# Schematic_STM32.net
KiCad netlist of a schematic drawn in Altium Designer
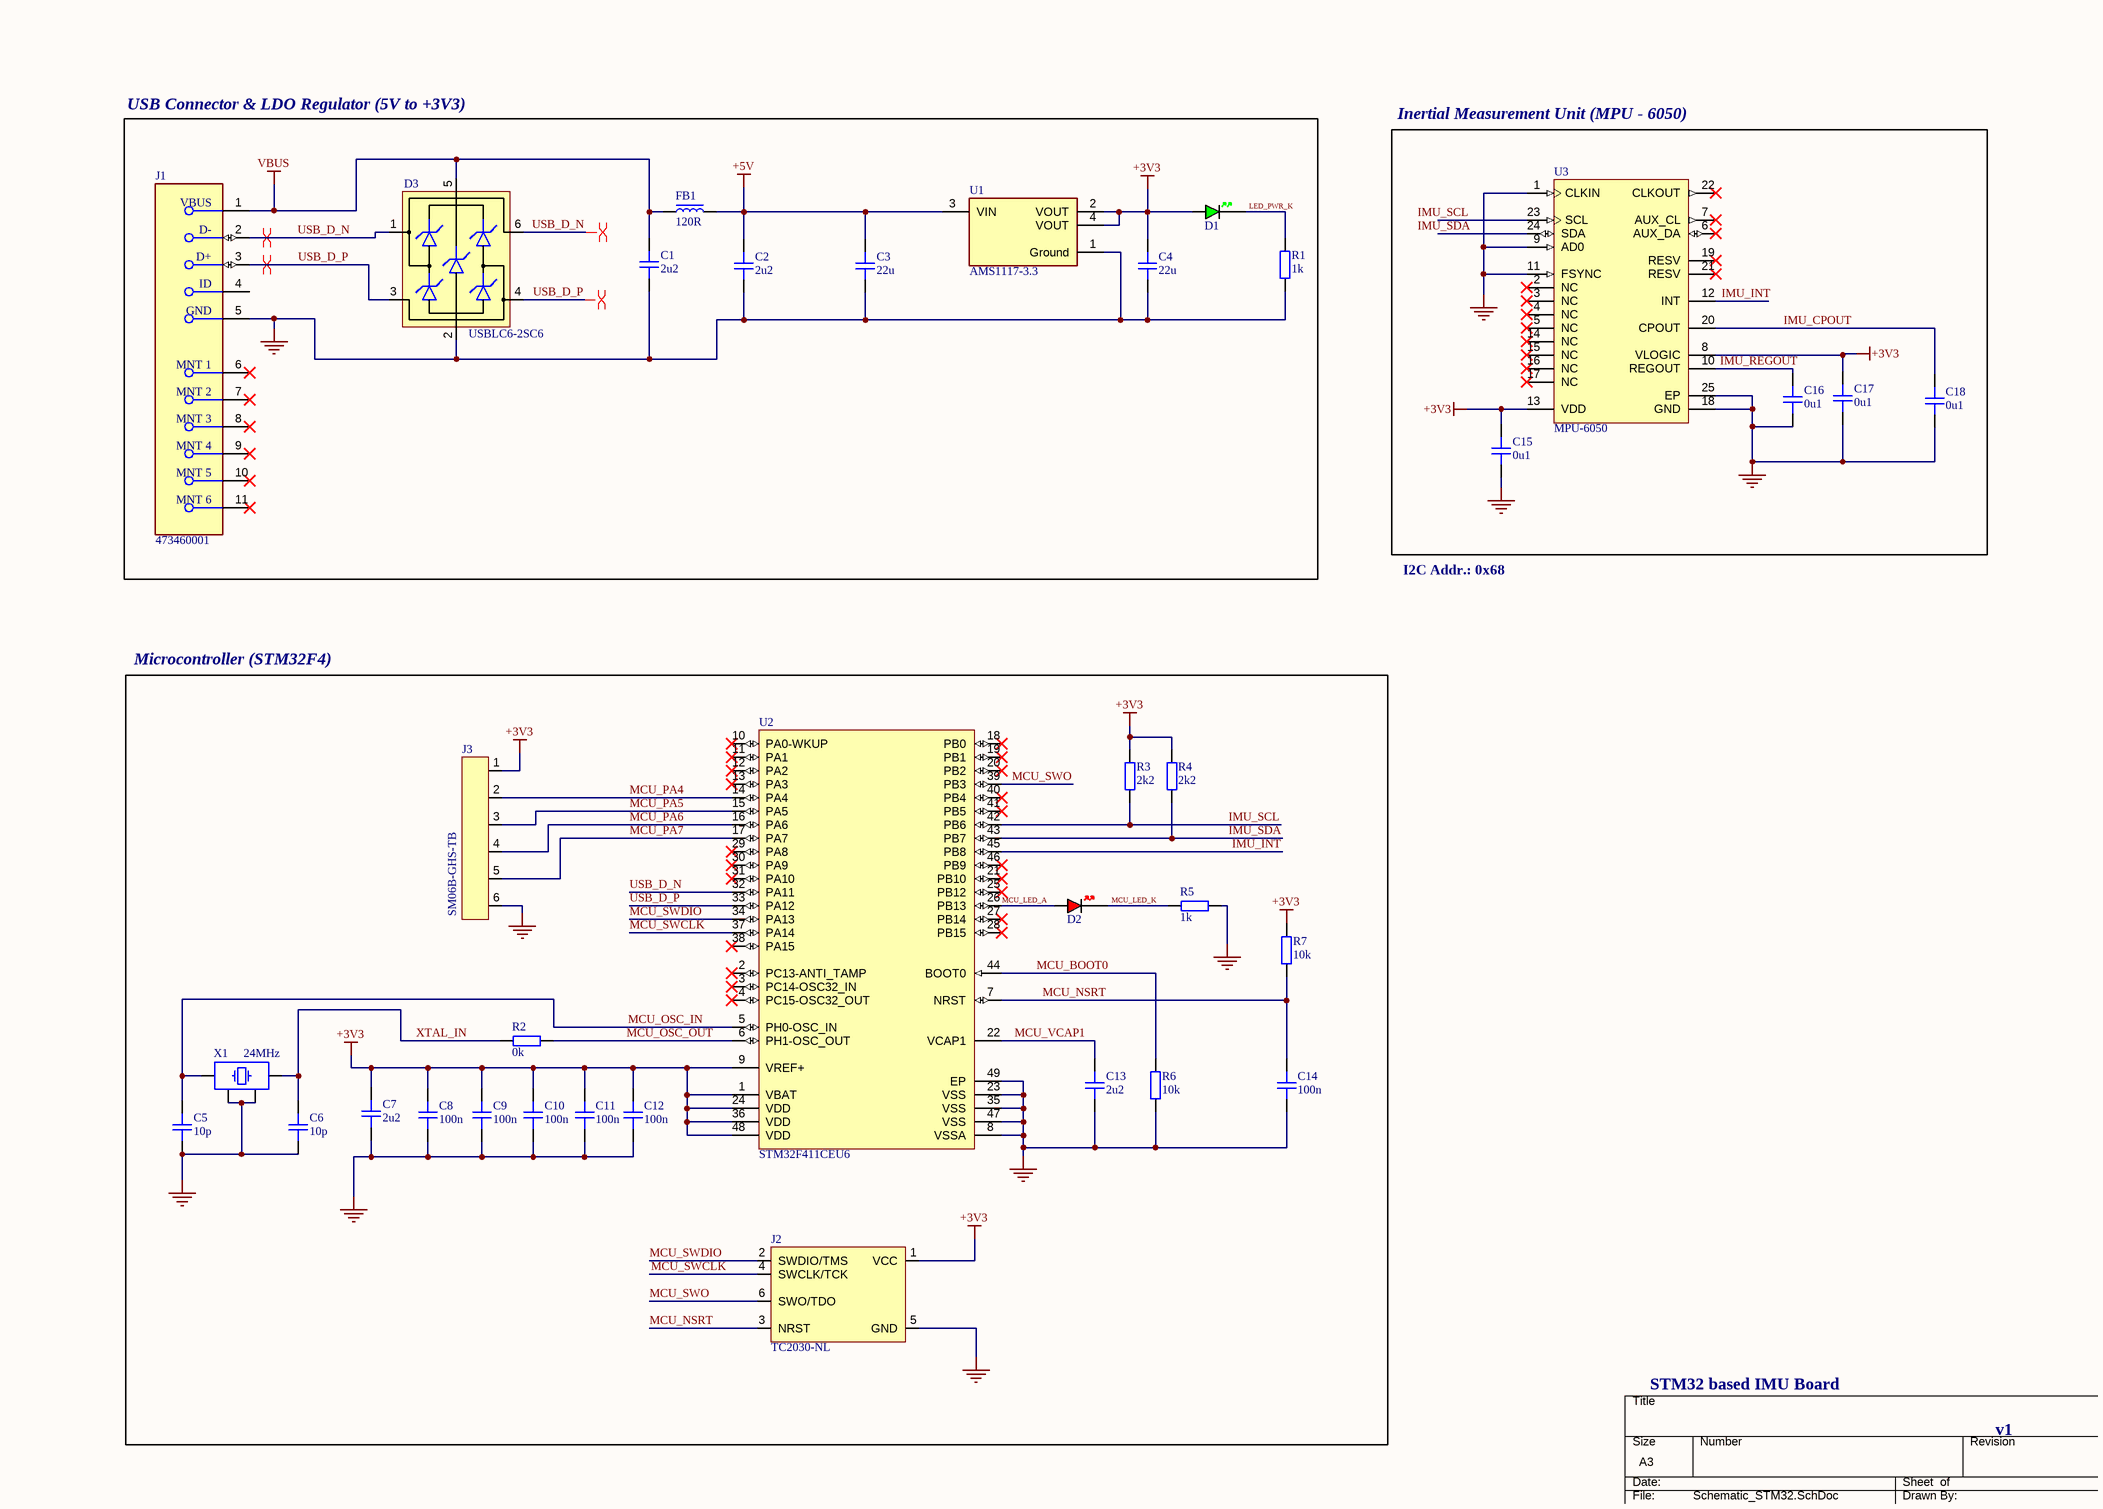
[diagram p0: Schematic_STM32.SchDoc]

(export (version "E")
  (design (tool "Eeschema 10.0.6"))
  (components
    (comp (ref "C1")
      (value "2u2")
      (footprint "CAP_0603")
      (description "Capacitor SMD 0603")
      (libsource (lib "Schematic-Lib-PhilsLab") (part "CAP_0603"))
    )
    (comp (ref "C2")
      (value "2u2")
      (footprint "CAP_0603")
      (description "Capacitor SMD 0603")
      (libsource (lib "Schematic-Lib-PhilsLab") (part "CAP_0603"))
    )
    (comp (ref "C3")
      (value "22u")
      (footprint "CAP_0805")
      (description "Capacitor SMD 0805")
      (libsource (lib "Schematic-Lib-PhilsLab") (part "CAP_0805"))
    )
    (comp (ref "C4")
      (value "22u")
      (footprint "CAP_0805")
      (description "Capacitor SMD 0805")
      (libsource (lib "Schematic-Lib-PhilsLab") (part "CAP_0805"))
    )
    (comp (ref "C5")
      (value "10p")
      (footprint "CAP_0402")
      (description "Capacitor SMD 0402")
      (libsource (lib "Schematic-Lib-PhilsLab") (part "CAP_0402"))
    )
    (comp (ref "C6")
      (value "10p")
      (footprint "CAP_0402")
      (description "Capacitor SMD 0402")
      (libsource (lib "Schematic-Lib-PhilsLab") (part "CAP_0402"))
    )
    (comp (ref "C7")
      (value "2u2")
      (footprint "CAP_0603")
      (description "Capacitor SMD 0603")
      (libsource (lib "Schematic-Lib-PhilsLab") (part "CAP_0603"))
    )
    (comp (ref "C8")
      (value "100n")
      (footprint "CAP_0402")
      (description "Capacitor SMD 0402")
      (libsource (lib "Schematic-Lib-PhilsLab") (part "CAP_0402"))
    )
    (comp (ref "C9")
      (value "100n")
      (footprint "CAP_0402")
      (description "Capacitor SMD 0402")
      (libsource (lib "Schematic-Lib-PhilsLab") (part "CAP_0402"))
    )
    (comp (ref "C10")
      (value "100n")
      (footprint "CAP_0402")
      (description "Capacitor SMD 0402")
      (libsource (lib "Schematic-Lib-PhilsLab") (part "CAP_0402"))
    )
    (comp (ref "C11")
      (value "100n")
      (footprint "CAP_0402")
      (description "Capacitor SMD 0402")
      (libsource (lib "Schematic-Lib-PhilsLab") (part "CAP_0402"))
    )
    (comp (ref "C12")
      (value "100n")
      (footprint "CAP_0402")
      (description "Capacitor SMD 0402")
      (libsource (lib "Schematic-Lib-PhilsLab") (part "CAP_0402"))
    )
    (comp (ref "C13")
      (value "2u2")
      (footprint "CAP_0603")
      (description "Capacitor SMD 0603")
      (libsource (lib "Schematic-Lib-PhilsLab") (part "CAP_0603"))
    )
    (comp (ref "C14")
      (value "100n")
      (footprint "CAP_0402")
      (description "Capacitor SMD 0402")
      (libsource (lib "Schematic-Lib-PhilsLab") (part "CAP_0402"))
    )
    (comp (ref "C15")
      (value "0u1")
      (footprint "CAP_0402")
      (description "Capacitor SMD 0402")
      (libsource (lib "Schematic-Lib-PhilsLab") (part "CAP_0402"))
    )
    (comp (ref "C16")
      (value "0u1")
      (footprint "CAP_0402")
      (description "Capacitor SMD 0402")
      (libsource (lib "Schematic-Lib-PhilsLab") (part "CAP_0402"))
    )
    (comp (ref "C17")
      (value "0u1")
      (footprint "CAP_0402")
      (description "Capacitor SMD 0402")
      (libsource (lib "Schematic-Lib-PhilsLab") (part "CAP_0402"))
    )
    (comp (ref "C18")
      (value "0u1")
      (footprint "CAP_0402")
      (description "Capacitor SMD 0402")
      (libsource (lib "Schematic-Lib-PhilsLab") (part "CAP_0402"))
    )
    (comp (ref "D1")
      (value "GREEN")
      (footprint "LED_0402_GREEN")
      (description "LED 0402 GREEN SMD")
      (libsource (lib "Schematic-Lib-PhilsLab") (part "LED_0402_GREEN"))
    )
    (comp (ref "D2")
      (value "RED")
      (footprint "LED_0402_RED")
      (description "LED 0402 RED SMD")
      (libsource (lib "Schematic-Lib-PhilsLab") (part "LED_0402_RED"))
    )
    (comp (ref "D3")
      (value "USBLC6-2SC6")
      (footprint "SOT-23-6")
      (description "Low-Capacitance ESD Protection USB")
      (fields (field (name "MANUFACTURER") "STMicroelectronics"))
      (libsource (lib "Schematic-Lib-PhilsLab") (part "USBLC6-2SC6"))
    )
    (comp (ref "FB1")
      (value "120R")
      (footprint "FB_0402")
      (description "Ferrite Bead SMD 0402")
      (libsource (lib "Schematic-Lib-PhilsLab") (part "FB_0402"))
    )
    (comp (ref "J1")
      (value "473460001")
      (footprint "FP-473460001-MFG")
      (description "CONN RCPT USB2.0 MICRO B SMD R/A")
      (fields
        (field (name "OCTOPART") "https://octopart.com/47346-0001-molex-7164928")
        (field (name "MANUFACTURER") "Molex")
      )
      (libsource (lib "Altium Content Vault") (part "53ae1f1d9b557310b43ca686e5bb76a"))
    )
    (comp (ref "J2")
      (value "TC2030-NL")
      (footprint "TC2030-NL-FP")
      (description "Tag-Connect No-Solder SWD Debug Connector (No Legs) DO NOT PLACE")
      (fields
        (field (name "MANUFACTURER") "Tag-Connect")
        (field (name "MANUFACTURER PART NUMBER") "TC2030-NL-FP")
      )
      (libsource (lib "Schematic-Lib-PhilsLab") (part "TC2030-NL"))
    )
    (comp (ref "J3")
      (value "SM06B-GHS-TB")
      (footprint "SM06B-GHS-TB")
      (description "Header Connector 6 Position 1.25MM Pitch SMD Horizontal JST GH")
      (fields (field (name "MANUFACTURER") "JST"))
      (libsource (lib "Schematic-Lib-PhilsLab") (part "SM06B-GHS-TB"))
    )
    (comp (ref "R1")
      (value "1k")
      (footprint "RES_0402")
      (description "Resistor SMD 0402")
      (libsource (lib "Schematic-Lib-PhilsLab") (part "RES_0402"))
    )
    (comp (ref "R2")
      (value "0k")
      (footprint "RES_0402")
      (description "Resistor SMD 0402")
      (libsource (lib "Schematic-Lib-PhilsLab") (part "RES_0402"))
    )
    (comp (ref "R3")
      (value "2k2")
      (footprint "RES_0402")
      (description "Resistor SMD 0402")
      (libsource (lib "Schematic-Lib-PhilsLab") (part "RES_0402"))
    )
    (comp (ref "R4")
      (value "2k2")
      (footprint "RES_0402")
      (description "Resistor SMD 0402")
      (libsource (lib "Schematic-Lib-PhilsLab") (part "RES_0402"))
    )
    (comp (ref "R5")
      (value "1k")
      (footprint "RES_0402")
      (description "Resistor SMD 0402")
      (libsource (lib "Schematic-Lib-PhilsLab") (part "RES_0402"))
    )
    (comp (ref "R6")
      (value "10k")
      (footprint "RES_0402")
      (description "Resistor SMD 0402")
      (libsource (lib "Schematic-Lib-PhilsLab") (part "RES_0402"))
    )
    (comp (ref "R7")
      (value "10k")
      (footprint "RES_0402")
      (description "Resistor SMD 0402")
      (libsource (lib "Schematic-Lib-PhilsLab") (part "RES_0402"))
    )
    (comp (ref "U1")
      (value "AMS1117-3.3")
      (footprint "FP-AMS1117-IPC_C")
      (description "LDO Voltage Regulators 1A, 3.3V")
      (fields
        (field (name "OCTOPART") "https://octopart.com/ams1117-3.3-advanced+monolithic+systems-25899300")
        (field (name "MANUFACTURER") "Advanced Monolithic Systems")
      )
      (libsource (lib "Altium Content Vault") (part "8bdbb5f8e77002000e30dd2845d0354"))
    )
    (comp (ref "U2")
      (value "STM32F411CEU6")
      (footprint "STM-UFQFPN48_L")
      (libsource (lib "Altium Content Vault") (part "MC-ARM-STM32F411-UFQFPN48"))
    )
    (comp (ref "U3")
      (value "MPU-6050")
      (footprint "IS-QFN-24_V")
      (fields (field (name "MANUFACTURER") "InvenSense"))
      (libsource (lib "Altium Content Vault") (part "IS-MPU-6050-QFN-24"))
    )
    (comp (ref "X1")
      (value "24MHz")
      (footprint "XTAL_3225")
      (description "Crystal SMD 24MHz 10PPM 7pF 3225")
      (fields
        (field (name "MANUFACTURER") "Epson")
        (field (name "MANUFACTURER PART NUMBER") "TSX-3225 24.0000MF15X-AC")
      )
      (libsource (lib "Schematic-Lib-PhilsLab") (part "TSX-3225_24.0000MF15X-AC"))
    )
  )
  (nets
    (net (code "1") (name "+3V3") (class "Default")
      (node (ref "C10") (pin "2") (pinfunction "2_2") (pintype "passive"))
      (node (ref "C11") (pin "2") (pinfunction "2_2") (pintype "passive"))
      (node (ref "C12") (pin "2") (pinfunction "2_2") (pintype "passive"))
      (node (ref "C15") (pin "2") (pinfunction "2_2") (pintype "passive"))
      (node (ref "C17") (pin "2") (pinfunction "2_2") (pintype "passive"))
      (node (ref "C4") (pin "2") (pinfunction "2_2") (pintype "passive"))
      (node (ref "C7") (pin "2") (pinfunction "2_2") (pintype "passive"))
      (node (ref "C8") (pin "2") (pinfunction "2_2") (pintype "passive"))
      (node (ref "C9") (pin "2") (pinfunction "2_2") (pintype "passive"))
      (node (ref "D1") (pin "A") (pinfunction "A_A") (pintype "passive"))
      (node (ref "J2") (pin "1") (pinfunction "VCC_1") (pintype "passive"))
      (node (ref "J3") (pin "1") (pinfunction "1_1") (pintype "passive"))
      (node (ref "R3") (pin "2") (pinfunction "2_2") (pintype "passive"))
      (node (ref "R4") (pin "2") (pinfunction "2_2") (pintype "passive"))
      (node (ref "R7") (pin "2") (pinfunction "2_2") (pintype "passive"))
      (node (ref "U1") (pin "2") (pinfunction "VOUT_2") (pintype "passive"))
      (node (ref "U1") (pin "4") (pinfunction "VOUT_4") (pintype "passive"))
      (node (ref "U2") (pin "1") (pinfunction "VBAT_1") (pintype "power_in"))
      (node (ref "U2") (pin "24") (pinfunction "VDD_24") (pintype "power_in"))
      (node (ref "U2") (pin "36") (pinfunction "VDD_36") (pintype "power_in"))
      (node (ref "U2") (pin "48") (pinfunction "VDD_48") (pintype "power_in"))
      (node (ref "U2") (pin "9") (pinfunction "VREF+_9") (pintype "power_in"))
      (node (ref "U3") (pin "13") (pinfunction "VDD_13") (pintype "power_in"))
      (node (ref "U3") (pin "8") (pinfunction "VLOGIC_8") (pintype "power_in"))
    )
    (net (code "2") (name "+5V") (class "Default")
      (node (ref "C2") (pin "2") (pinfunction "2_2") (pintype "passive"))
      (node (ref "C3") (pin "2") (pinfunction "2_2") (pintype "passive"))
      (node (ref "FB1") (pin "2") (pinfunction "2_2") (pintype "passive"))
      (node (ref "U1") (pin "3") (pinfunction "VIN_3") (pintype "power_in"))
    )
    (net (code "3") (name "/IMU_CPOUT") (class "Default")
      (node (ref "C18") (pin "2") (pinfunction "2_2") (pintype "passive"))
      (node (ref "U3") (pin "20") (pinfunction "CPOUT_20") (pintype "passive"))
    )
    (net (code "4") (name "/IMU_INT") (class "Default")
      (node (ref "U2") (pin "45") (pinfunction "PB8_45") (pintype "bidirectional"))
      (node (ref "U3") (pin "12") (pinfunction "INT_12") (pintype "open_collector"))
    )
    (net (code "5") (name "/IMU_REGOUT") (class "Default")
      (node (ref "C16") (pin "2") (pinfunction "2_2") (pintype "passive"))
      (node (ref "U3") (pin "10") (pinfunction "REGOUT_10") (pintype "passive"))
    )
    (net (code "6") (name "/IMU_SCL") (class "Default")
      (node (ref "R3") (pin "1") (pinfunction "1_1") (pintype "passive"))
      (node (ref "U2") (pin "42") (pinfunction "PB6_42") (pintype "bidirectional"))
      (node (ref "U3") (pin "23") (pinfunction "SCL_23") (pintype "input"))
    )
    (net (code "7") (name "/IMU_SDA") (class "Default")
      (node (ref "R4") (pin "1") (pinfunction "1_1") (pintype "passive"))
      (node (ref "U2") (pin "43") (pinfunction "PB7_43") (pintype "bidirectional"))
      (node (ref "U3") (pin "24") (pinfunction "SDA_24") (pintype "bidirectional"))
    )
    (net (code "8") (name "/LED_PWR_K") (class "Default")
      (node (ref "D1") (pin "K") (pinfunction "K_K") (pintype "passive"))
      (node (ref "R1") (pin "2") (pinfunction "2_2") (pintype "passive"))
    )
    (net (code "9") (name "/MCU_BOOT0") (class "Default")
      (node (ref "R6") (pin "2") (pinfunction "2_2") (pintype "passive"))
      (node (ref "U2") (pin "44") (pinfunction "BOOT0_44") (pintype "input"))
    )
    (net (code "10") (name "/MCU_LED_A") (class "Default")
      (node (ref "D2") (pin "A") (pinfunction "A_A") (pintype "passive"))
      (node (ref "U2") (pin "26") (pinfunction "PB13_26") (pintype "bidirectional"))
    )
    (net (code "11") (name "/MCU_LED_K") (class "Default")
      (node (ref "D2") (pin "K") (pinfunction "K_K") (pintype "passive"))
      (node (ref "R5") (pin "2") (pinfunction "2_2") (pintype "passive"))
    )
    (net (code "12") (name "/MCU_NSRT") (class "Default")
      (node (ref "C14") (pin "2") (pinfunction "2_2") (pintype "passive"))
      (node (ref "J2") (pin "3") (pinfunction "NRST_3") (pintype "passive"))
      (node (ref "R7") (pin "1") (pinfunction "1_1") (pintype "passive"))
      (node (ref "U2") (pin "7") (pinfunction "NRST_7") (pintype "bidirectional"))
    )
    (net (code "13") (name "/MCU_OSC_IN") (class "Default")
      (node (ref "C5") (pin "2") (pinfunction "2_2") (pintype "passive"))
      (node (ref "U2") (pin "5") (pinfunction "PH0-OSC_IN_5") (pintype "bidirectional"))
      (node (ref "X1") (pin "1") (pinfunction "1_1") (pintype "passive"))
    )
    (net (code "14") (name "/MCU_OSC_OUT") (class "Default")
      (node (ref "R2") (pin "1") (pinfunction "1_1") (pintype "passive"))
      (node (ref "U2") (pin "6") (pinfunction "PH1-OSC_OUT_6") (pintype "bidirectional"))
    )
    (net (code "15") (name "/MCU_PA4") (class "Default")
      (node (ref "J3") (pin "2") (pinfunction "2_2") (pintype "passive"))
      (node (ref "U2") (pin "14") (pinfunction "PA4_14") (pintype "bidirectional"))
    )
    (net (code "16") (name "/MCU_PA5") (class "Default")
      (node (ref "J3") (pin "3") (pinfunction "3_3") (pintype "passive"))
      (node (ref "U2") (pin "15") (pinfunction "PA5_15") (pintype "bidirectional"))
    )
    (net (code "17") (name "/MCU_PA6") (class "Default")
      (node (ref "J3") (pin "4") (pinfunction "4_4") (pintype "passive"))
      (node (ref "U2") (pin "16") (pinfunction "PA6_16") (pintype "bidirectional"))
    )
    (net (code "18") (name "/MCU_PA7") (class "Default")
      (node (ref "J3") (pin "5") (pinfunction "5_5") (pintype "passive"))
      (node (ref "U2") (pin "17") (pinfunction "PA7_17") (pintype "bidirectional"))
    )
    (net (code "19") (name "/MCU_SWCLK") (class "Default")
      (node (ref "J2") (pin "4") (pinfunction "SWCLK/TCK_4") (pintype "passive"))
      (node (ref "U2") (pin "37") (pinfunction "PA14_37") (pintype "bidirectional"))
    )
    (net (code "20") (name "/MCU_SWDIO") (class "Default")
      (node (ref "J2") (pin "2") (pinfunction "SWDIO/TMS_2") (pintype "passive"))
      (node (ref "U2") (pin "34") (pinfunction "PA13_34") (pintype "bidirectional"))
    )
    (net (code "21") (name "/MCU_SWO") (class "Default")
      (node (ref "J2") (pin "6") (pinfunction "SWO/TDO_6") (pintype "passive"))
      (node (ref "U2") (pin "39") (pinfunction "PB3_39") (pintype "bidirectional"))
    )
    (net (code "22") (name "/MCU_VCAP1") (class "Default")
      (node (ref "C13") (pin "2") (pinfunction "2_2") (pintype "passive"))
      (node (ref "U2") (pin "22") (pinfunction "VCAP1_22") (pintype "passive"))
    )
    (net (code "23") (name "/USB_D_N") (class "Default")
      (node (ref "D3") (pin "1") (pinfunction "IO1_1") (pintype "bidirectional"))
      (node (ref "D3") (pin "6") (pinfunction "IO1_6") (pintype "bidirectional"))
      (node (ref "J1") (pin "2") (pinfunction "D-_2") (pintype "bidirectional"))
      (node (ref "U2") (pin "32") (pinfunction "PA11_32") (pintype "bidirectional"))
    )
    (net (code "24") (name "/USB_D_P") (class "Default")
      (node (ref "D3") (pin "3") (pinfunction "IO2_3") (pintype "bidirectional"))
      (node (ref "D3") (pin "4") (pinfunction "IO2_4") (pintype "bidirectional"))
      (node (ref "J1") (pin "3") (pinfunction "D+_3") (pintype "bidirectional"))
      (node (ref "U2") (pin "33") (pinfunction "PA12_33") (pintype "bidirectional"))
    )
    (net (code "25") (name "/XTAL_IN") (class "Default")
      (node (ref "C6") (pin "2") (pinfunction "2_2") (pintype "passive"))
      (node (ref "R2") (pin "2") (pinfunction "2_2") (pintype "passive"))
      (node (ref "X1") (pin "3") (pinfunction "3_3") (pintype "passive"))
    )
    (net (code "26") (name "GND") (class "Default")
      (node (ref "C1") (pin "1") (pinfunction "1_1") (pintype "passive"))
      (node (ref "C10") (pin "1") (pinfunction "1_1") (pintype "passive"))
      (node (ref "C11") (pin "1") (pinfunction "1_1") (pintype "passive"))
      (node (ref "C12") (pin "1") (pinfunction "1_1") (pintype "passive"))
      (node (ref "C13") (pin "1") (pinfunction "1_1") (pintype "passive"))
      (node (ref "C14") (pin "1") (pinfunction "1_1") (pintype "passive"))
      (node (ref "C15") (pin "1") (pinfunction "1_1") (pintype "passive"))
      (node (ref "C16") (pin "1") (pinfunction "1_1") (pintype "passive"))
      (node (ref "C17") (pin "1") (pinfunction "1_1") (pintype "passive"))
      (node (ref "C18") (pin "1") (pinfunction "1_1") (pintype "passive"))
      (node (ref "C2") (pin "1") (pinfunction "1_1") (pintype "passive"))
      (node (ref "C3") (pin "1") (pinfunction "1_1") (pintype "passive"))
      (node (ref "C4") (pin "1") (pinfunction "1_1") (pintype "passive"))
      (node (ref "C5") (pin "1") (pinfunction "1_1") (pintype "passive"))
      (node (ref "C6") (pin "1") (pinfunction "1_1") (pintype "passive"))
      (node (ref "C7") (pin "1") (pinfunction "1_1") (pintype "passive"))
      (node (ref "C8") (pin "1") (pinfunction "1_1") (pintype "passive"))
      (node (ref "C9") (pin "1") (pinfunction "1_1") (pintype "passive"))
      (node (ref "D3") (pin "2") (pinfunction "GND_2") (pintype "power_in"))
      (node (ref "J1") (pin "5") (pinfunction "GND_5") (pintype "power_in"))
      (node (ref "J2") (pin "5") (pinfunction "GND_5") (pintype "passive"))
      (node (ref "J3") (pin "6") (pinfunction "6_6") (pintype "passive"))
      (node (ref "R1") (pin "1") (pinfunction "1_1") (pintype "passive"))
      (node (ref "R5") (pin "1") (pinfunction "1_1") (pintype "passive"))
      (node (ref "R6") (pin "1") (pinfunction "1_1") (pintype "passive"))
      (node (ref "U1") (pin "1") (pinfunction "Ground_1") (pintype "power_in"))
      (node (ref "U2") (pin "23") (pinfunction "VSS_23") (pintype "power_in"))
      (node (ref "U2") (pin "35") (pinfunction "VSS_35") (pintype "power_in"))
      (node (ref "U2") (pin "47") (pinfunction "VSS_47") (pintype "power_in"))
      (node (ref "U2") (pin "49") (pinfunction "EP_49") (pintype "power_in"))
      (node (ref "U2") (pin "8") (pinfunction "VSSA_8") (pintype "power_in"))
      (node (ref "U3") (pin "1") (pinfunction "CLKIN_1") (pintype "input"))
      (node (ref "U3") (pin "11") (pinfunction "FSYNC_11") (pintype "input"))
      (node (ref "U3") (pin "18") (pinfunction "GND_18") (pintype "power_in"))
      (node (ref "U3") (pin "25") (pinfunction "EP_25") (pintype "power_in"))
      (node (ref "U3") (pin "9") (pinfunction "AD0_9") (pintype "input"))
      (node (ref "X1") (pin "2") (pinfunction "2_2") (pintype "passive"))
      (node (ref "X1") (pin "4") (pinfunction "4_4") (pintype "passive"))
    )
    (net (code "27") (name "VBUS") (class "Default")
      (node (ref "C1") (pin "2") (pinfunction "2_2") (pintype "passive"))
      (node (ref "D3") (pin "5") (pinfunction "VBUS_5") (pintype "power_in"))
      (node (ref "FB1") (pin "1") (pinfunction "1_1") (pintype "passive"))
      (node (ref "J1") (pin "1") (pinfunction "VBUS_1") (pintype "power_in"))
    )
    (net (code "28") (name "unconnected-(J1-ID-Pad4)") (class "Default")
      (node (ref "J1") (pin "4") (pinfunction "ID_4") (pintype "passive"))
    )
    (net (code "29") (name "unconnected-(J1-MNT_1-Pad6)") (class "Default")
      (node (ref "J1") (pin "6") (pinfunction "MNT_1_6") (pintype "passive+no_connect"))
    )
    (net (code "30") (name "unconnected-(J1-MNT_2-Pad7)") (class "Default")
      (node (ref "J1") (pin "7") (pinfunction "MNT_2_7") (pintype "passive+no_connect"))
    )
    (net (code "31") (name "unconnected-(J1-MNT_3-Pad8)") (class "Default")
      (node (ref "J1") (pin "8") (pinfunction "MNT_3_8") (pintype "passive+no_connect"))
    )
    (net (code "32") (name "unconnected-(J1-MNT_4-Pad9)") (class "Default")
      (node (ref "J1") (pin "9") (pinfunction "MNT_4_9") (pintype "passive+no_connect"))
    )
    (net (code "33") (name "unconnected-(J1-MNT_5-Pad10)") (class "Default")
      (node (ref "J1") (pin "10") (pinfunction "MNT_5_10") (pintype "passive+no_connect"))
    )
    (net (code "34") (name "unconnected-(J1-MNT_6-Pad11)") (class "Default")
      (node (ref "J1") (pin "11") (pinfunction "MNT_6_11") (pintype "passive+no_connect"))
    )
    (net (code "35") (name "unconnected-(U2-PA0-WKUP-Pad10)") (class "Default")
      (node (ref "U2") (pin "10") (pinfunction "PA0-WKUP_10") (pintype "bidirectional+no_connect"))
    )
    (net (code "36") (name "unconnected-(U2-PA1-Pad11)") (class "Default")
      (node (ref "U2") (pin "11") (pinfunction "PA1_11") (pintype "bidirectional+no_connect"))
    )
    (net (code "37") (name "unconnected-(U2-PA2-Pad12)") (class "Default")
      (node (ref "U2") (pin "12") (pinfunction "PA2_12") (pintype "bidirectional+no_connect"))
    )
    (net (code "38") (name "unconnected-(U2-PA3-Pad13)") (class "Default")
      (node (ref "U2") (pin "13") (pinfunction "PA3_13") (pintype "bidirectional+no_connect"))
    )
    (net (code "39") (name "unconnected-(U2-PA8-Pad29)") (class "Default")
      (node (ref "U2") (pin "29") (pinfunction "PA8_29") (pintype "bidirectional+no_connect"))
    )
    (net (code "40") (name "unconnected-(U2-PA9-Pad30)") (class "Default")
      (node (ref "U2") (pin "30") (pinfunction "PA9_30") (pintype "bidirectional+no_connect"))
    )
    (net (code "41") (name "unconnected-(U2-PA10-Pad31)") (class "Default")
      (node (ref "U2") (pin "31") (pinfunction "PA10_31") (pintype "bidirectional+no_connect"))
    )
    (net (code "42") (name "unconnected-(U2-PA15-Pad38)") (class "Default")
      (node (ref "U2") (pin "38") (pinfunction "PA15_38") (pintype "bidirectional+no_connect"))
    )
    (net (code "43") (name "unconnected-(U2-PB0-Pad18)") (class "Default")
      (node (ref "U2") (pin "18") (pinfunction "PB0_18") (pintype "bidirectional+no_connect"))
    )
    (net (code "44") (name "unconnected-(U2-PB1-Pad19)") (class "Default")
      (node (ref "U2") (pin "19") (pinfunction "PB1_19") (pintype "bidirectional+no_connect"))
    )
    (net (code "45") (name "unconnected-(U2-PB2-Pad20)") (class "Default")
      (node (ref "U2") (pin "20") (pinfunction "PB2_20") (pintype "bidirectional+no_connect"))
    )
    (net (code "46") (name "unconnected-(U2-PB4-Pad40)") (class "Default")
      (node (ref "U2") (pin "40") (pinfunction "PB4_40") (pintype "bidirectional+no_connect"))
    )
    (net (code "47") (name "unconnected-(U2-PB5-Pad41)") (class "Default")
      (node (ref "U2") (pin "41") (pinfunction "PB5_41") (pintype "bidirectional+no_connect"))
    )
    (net (code "48") (name "unconnected-(U2-PB9-Pad46)") (class "Default")
      (node (ref "U2") (pin "46") (pinfunction "PB9_46") (pintype "bidirectional+no_connect"))
    )
    (net (code "49") (name "unconnected-(U2-PB10-Pad21)") (class "Default")
      (node (ref "U2") (pin "21") (pinfunction "PB10_21") (pintype "bidirectional+no_connect"))
    )
    (net (code "50") (name "unconnected-(U2-PB12-Pad25)") (class "Default")
      (node (ref "U2") (pin "25") (pinfunction "PB12_25") (pintype "bidirectional+no_connect"))
    )
    (net (code "51") (name "unconnected-(U2-PB14-Pad27)") (class "Default")
      (node (ref "U2") (pin "27") (pinfunction "PB14_27") (pintype "bidirectional+no_connect"))
    )
    (net (code "52") (name "unconnected-(U2-PB15-Pad28)") (class "Default")
      (node (ref "U2") (pin "28") (pinfunction "PB15_28") (pintype "bidirectional+no_connect"))
    )
    (net (code "53") (name "unconnected-(U2-PC13-ANTI_TAMP-Pad2)") (class "Default")
      (node (ref "U2") (pin "2") (pinfunction "PC13-ANTI_TAMP_2") (pintype "bidirectional+no_connect"))
    )
    (net (code "54") (name "unconnected-(U2-PC14-OSC32_IN-Pad3)") (class "Default")
      (node (ref "U2") (pin "3") (pinfunction "PC14-OSC32_IN_3") (pintype "bidirectional+no_connect"))
    )
    (net (code "55") (name "unconnected-(U2-PC15-OSC32_OUT-Pad4)") (class "Default")
      (node (ref "U2") (pin "4") (pinfunction "PC15-OSC32_OUT_4") (pintype "bidirectional+no_connect"))
    )
    (net (code "56") (name "unconnected-(U3-AUX_CL-Pad7)") (class "Default")
      (node (ref "U3") (pin "7") (pinfunction "AUX_CL_7") (pintype "output+no_connect"))
    )
    (net (code "57") (name "unconnected-(U3-AUX_DA-Pad6)") (class "Default")
      (node (ref "U3") (pin "6") (pinfunction "AUX_DA_6") (pintype "bidirectional+no_connect"))
    )
    (net (code "58") (name "unconnected-(U3-CLKOUT-Pad22)") (class "Default")
      (node (ref "U3") (pin "22") (pinfunction "CLKOUT_22") (pintype "output+no_connect"))
    )
    (net (code "59") (name "unconnected-(U3-NC-Pad2)") (class "Default")
      (node (ref "U3") (pin "2") (pinfunction "NC_2") (pintype "passive+no_connect"))
    )
    (net (code "60") (name "unconnected-(U3-NC-Pad3)") (class "Default")
      (node (ref "U3") (pin "3") (pinfunction "NC_3") (pintype "passive+no_connect"))
    )
    (net (code "61") (name "unconnected-(U3-NC-Pad4)") (class "Default")
      (node (ref "U3") (pin "4") (pinfunction "NC_4") (pintype "passive+no_connect"))
    )
    (net (code "62") (name "unconnected-(U3-NC-Pad5)") (class "Default")
      (node (ref "U3") (pin "5") (pinfunction "NC_5") (pintype "passive+no_connect"))
    )
    (net (code "63") (name "unconnected-(U3-NC-Pad14)") (class "Default")
      (node (ref "U3") (pin "14") (pinfunction "NC_14") (pintype "passive+no_connect"))
    )
    (net (code "64") (name "unconnected-(U3-NC-Pad15)") (class "Default")
      (node (ref "U3") (pin "15") (pinfunction "NC_15") (pintype "passive+no_connect"))
    )
    (net (code "65") (name "unconnected-(U3-NC-Pad16)") (class "Default")
      (node (ref "U3") (pin "16") (pinfunction "NC_16") (pintype "passive+no_connect"))
    )
    (net (code "66") (name "unconnected-(U3-NC-Pad17)") (class "Default")
      (node (ref "U3") (pin "17") (pinfunction "NC_17") (pintype "passive+no_connect"))
    )
    (net (code "67") (name "unconnected-(U3-RESV-Pad19)") (class "Default")
      (node (ref "U3") (pin "19") (pinfunction "RESV_19") (pintype "passive+no_connect"))
    )
    (net (code "68") (name "unconnected-(U3-RESV-Pad21)") (class "Default")
      (node (ref "U3") (pin "21") (pinfunction "RESV_21") (pintype "passive+no_connect"))
    )
  )
)
